# Z05_C8V_02.net
KiCad netlist of a schematic drawn in EAGLE
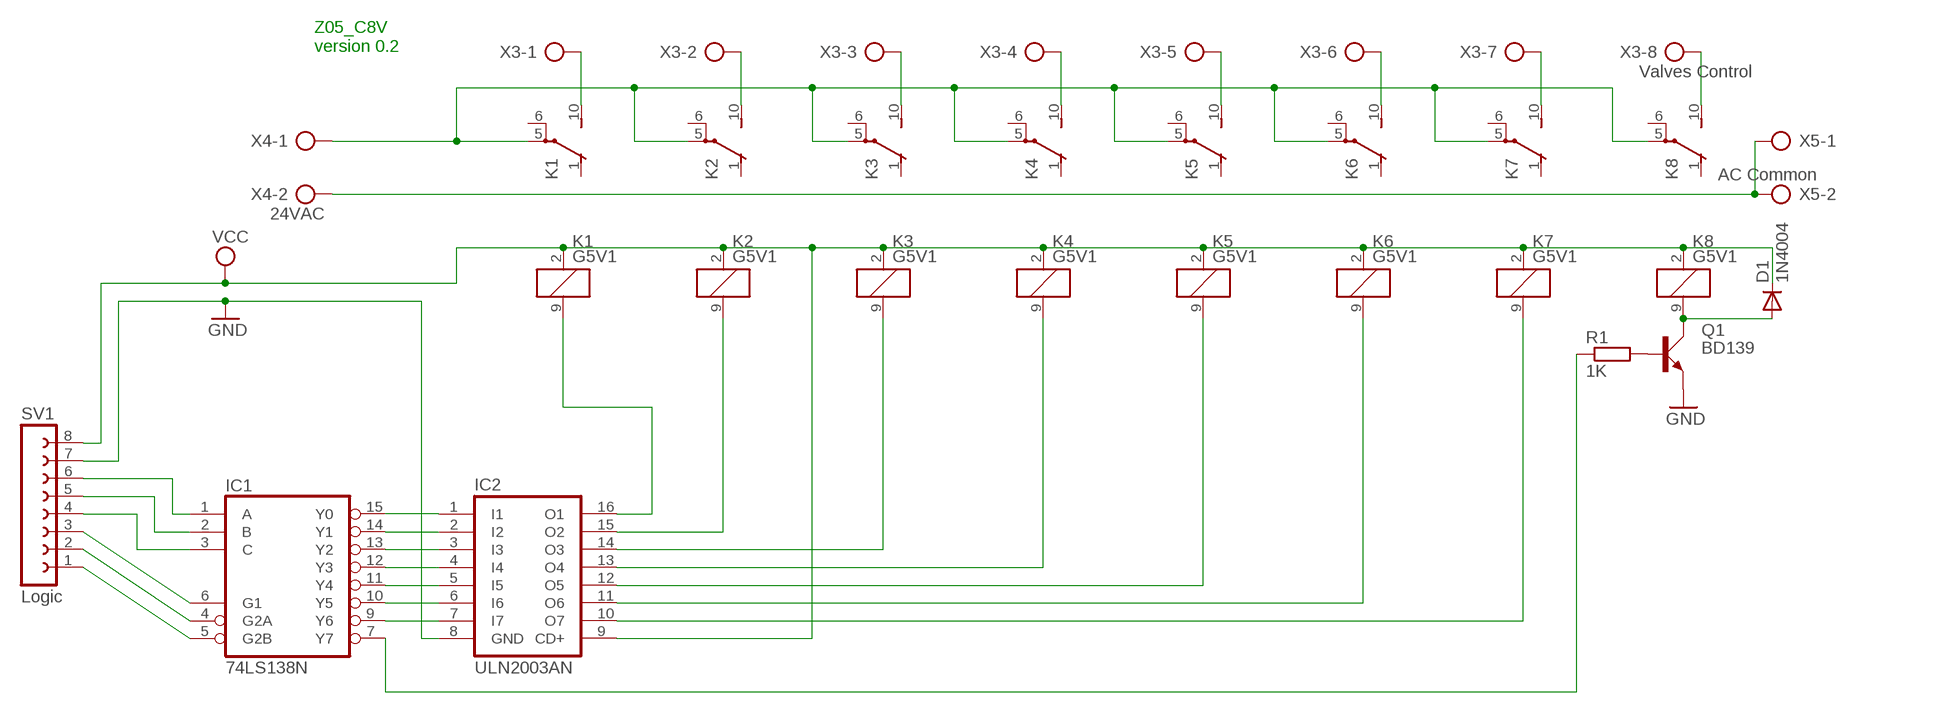
[diagram p0: schematic, sheet 1]

(export (version "E")
  (design (tool "Eeschema 10.0.6"))
  (components
    (comp (ref "D1")
      (value "1N4004")
      (footprint "eagle-import:DO41-10")
      (libsource (lib "eagle-import") (part "1N4004"))
    )
    (comp (ref "IC1")
      (value "74LS138N")
      (footprint "eagle-import:DIL16")
      (libsource (lib "eagle-import") (part "74138NLS"))
    )
    (comp (ref "IC2")
      (value "ULN2003AN")
      (footprint "eagle-import:DIL16")
      (libsource (lib "eagle-import") (part "ULN2003AN"))
    )
    (comp (ref "K1")
      (value "G5V1")
      (footprint "eagle-import:G5V1")
      (fields (field (name "MPN") "G5V-1-DC24"))
      (libsource (lib "eagle-import") (part "G5V1"))
    )
    (comp (ref "K2")
      (value "G5V1")
      (footprint "eagle-import:G5V1")
      (fields (field (name "MPN") "G5V-1-DC24"))
      (libsource (lib "eagle-import") (part "G5V1"))
    )
    (comp (ref "K3")
      (value "G5V1")
      (footprint "eagle-import:G5V1")
      (fields (field (name "MPN") "G5V-1-DC24"))
      (libsource (lib "eagle-import") (part "G5V1"))
    )
    (comp (ref "K4")
      (value "G5V1")
      (footprint "eagle-import:G5V1")
      (fields (field (name "MPN") "G5V-1-DC24"))
      (libsource (lib "eagle-import") (part "G5V1"))
    )
    (comp (ref "K5")
      (value "G5V1")
      (footprint "eagle-import:G5V1")
      (fields (field (name "MPN") "G5V-1-DC24"))
      (libsource (lib "eagle-import") (part "G5V1"))
    )
    (comp (ref "K6")
      (value "G5V1")
      (footprint "eagle-import:G5V1")
      (fields (field (name "MPN") "G5V-1-DC24"))
      (libsource (lib "eagle-import") (part "G5V1"))
    )
    (comp (ref "K7")
      (value "G5V1")
      (footprint "eagle-import:G5V1")
      (fields (field (name "MPN") "G5V-1-DC24"))
      (libsource (lib "eagle-import") (part "G5V1"))
    )
    (comp (ref "K8")
      (value "G5V1")
      (footprint "eagle-import:G5V1")
      (fields (field (name "MPN") "G5V-1-DC24"))
      (libsource (lib "eagle-import") (part "G5V1"))
    )
    (comp (ref "Q1")
      (value "BD139")
      (footprint "eagle-import:TO126AV")
      (libsource (lib "eagle-import") (part "BD139"))
    )
    (comp (ref "R1")
      (value "1K")
      (footprint "eagle-import:0204_7")
      (libsource (lib "eagle-import") (part "R-EU_0204/7"))
    )
    (comp (ref "SV1")
      (value "Logic")
      (footprint "eagle-import:FE08")
      (libsource (lib "eagle-import") (part "FE08-1"))
    )
    (comp (ref "X3")
      (value "Valves Control")
      (footprint "eagle-import:AK500_8")
      (libsource (lib "eagle-import") (part "AK500/8"))
    )
    (comp (ref "X4")
      (value "24VAC")
      (footprint "eagle-import:AK500_2")
      (libsource (lib "eagle-import") (part "AK500/2"))
    )
    (comp (ref "X5")
      (value "AC Common")
      (footprint "eagle-import:AK500_2")
      (libsource (lib "eagle-import") (part "AK500/2"))
    )
  )
  (nets
    (net (code "1") (name "GND") (class "Default")
      (node (ref "IC2") (pin "8") (pinfunction "GND_8") (pintype "power_in"))
      (node (ref "Q1") (pin "E") (pinfunction "E_E") (pintype "passive"))
      (node (ref "SV1") (pin "7") (pinfunction "7_7") (pintype "passive"))
    )
    (net (code "2") (name "Net-(IC1A-A)") (class "Default")
      (node (ref "IC1") (pin "1") (pinfunction "A_1") (pintype "input"))
      (node (ref "SV1") (pin "6") (pinfunction "6_6") (pintype "passive"))
    )
    (net (code "3") (name "Net-(IC1A-B)") (class "Default")
      (node (ref "IC1") (pin "2") (pinfunction "B_2") (pintype "input"))
      (node (ref "SV1") (pin "5") (pinfunction "5_5") (pintype "passive"))
    )
    (net (code "4") (name "Net-(IC1A-C)") (class "Default")
      (node (ref "IC1") (pin "3") (pinfunction "C_3") (pintype "input"))
      (node (ref "SV1") (pin "4") (pinfunction "4_4") (pintype "passive"))
    )
    (net (code "5") (name "Net-(IC1A-G1)") (class "Default")
      (node (ref "IC1") (pin "6") (pinfunction "G1_6") (pintype "input"))
      (node (ref "SV1") (pin "3") (pinfunction "3_3") (pintype "passive"))
    )
    (net (code "6") (name "Net-(IC1A-G2A)") (class "Default")
      (node (ref "IC1") (pin "4") (pinfunction "G2A_4") (pintype "input"))
      (node (ref "SV1") (pin "2") (pinfunction "2_2") (pintype "passive"))
    )
    (net (code "7") (name "Net-(IC1A-G2B)") (class "Default")
      (node (ref "IC1") (pin "5") (pinfunction "G2B_5") (pintype "input"))
      (node (ref "SV1") (pin "1") (pinfunction "1_1") (pintype "passive"))
    )
    (net (code "8") (name "Net-(IC1A-Y0)") (class "Default")
      (node (ref "IC1") (pin "15") (pinfunction "Y0_15") (pintype "output"))
      (node (ref "IC2") (pin "1") (pinfunction "I1_1") (pintype "input"))
    )
    (net (code "9") (name "Net-(IC1A-Y1)") (class "Default")
      (node (ref "IC1") (pin "14") (pinfunction "Y1_14") (pintype "output"))
      (node (ref "IC2") (pin "2") (pinfunction "I2_2") (pintype "input"))
    )
    (net (code "10") (name "Net-(IC1A-Y2)") (class "Default")
      (node (ref "IC1") (pin "13") (pinfunction "Y2_13") (pintype "output"))
      (node (ref "IC2") (pin "3") (pinfunction "I3_3") (pintype "input"))
    )
    (net (code "11") (name "Net-(IC1A-Y3)") (class "Default")
      (node (ref "IC1") (pin "12") (pinfunction "Y3_12") (pintype "output"))
      (node (ref "IC2") (pin "4") (pinfunction "I4_4") (pintype "input"))
    )
    (net (code "12") (name "Net-(IC1A-Y4)") (class "Default")
      (node (ref "IC1") (pin "11") (pinfunction "Y4_11") (pintype "output"))
      (node (ref "IC2") (pin "5") (pinfunction "I5_5") (pintype "input"))
    )
    (net (code "13") (name "Net-(IC1A-Y5)") (class "Default")
      (node (ref "IC1") (pin "10") (pinfunction "Y5_10") (pintype "output"))
      (node (ref "IC2") (pin "6") (pinfunction "I6_6") (pintype "input"))
    )
    (net (code "14") (name "Net-(IC1A-Y6)") (class "Default")
      (node (ref "IC1") (pin "9") (pinfunction "Y6_9") (pintype "output"))
      (node (ref "IC2") (pin "7") (pinfunction "I7_7") (pintype "input"))
    )
    (net (code "15") (name "Net-(IC1A-Y7)") (class "Default")
      (node (ref "IC1") (pin "7") (pinfunction "Y7_7") (pintype "output"))
      (node (ref "R1") (pin "1") (pinfunction "1_1") (pintype "passive"))
    )
    (net (code "16") (name "Net-(IC2-O1)") (class "Default")
      (node (ref "IC2") (pin "16") (pinfunction "O1_16") (pintype "open_collector"))
      (node (ref "K1") (pin "9") (pinfunction "2_9") (pintype "passive"))
    )
    (net (code "17") (name "Net-(IC2-O2)") (class "Default")
      (node (ref "IC2") (pin "15") (pinfunction "O2_15") (pintype "open_collector"))
      (node (ref "K2") (pin "9") (pinfunction "2_9") (pintype "passive"))
    )
    (net (code "18") (name "Net-(IC2-O3)") (class "Default")
      (node (ref "IC2") (pin "14") (pinfunction "O3_14") (pintype "open_collector"))
      (node (ref "K3") (pin "9") (pinfunction "2_9") (pintype "passive"))
    )
    (net (code "19") (name "Net-(IC2-O4)") (class "Default")
      (node (ref "IC2") (pin "13") (pinfunction "O4_13") (pintype "open_collector"))
      (node (ref "K4") (pin "9") (pinfunction "2_9") (pintype "passive"))
    )
    (net (code "20") (name "Net-(IC2-O5)") (class "Default")
      (node (ref "IC2") (pin "12") (pinfunction "O5_12") (pintype "open_collector"))
      (node (ref "K5") (pin "9") (pinfunction "2_9") (pintype "passive"))
    )
    (net (code "21") (name "Net-(IC2-O6)") (class "Default")
      (node (ref "IC2") (pin "11") (pinfunction "O6_11") (pintype "open_collector"))
      (node (ref "K6") (pin "9") (pinfunction "2_9") (pintype "passive"))
    )
    (net (code "22") (name "Net-(IC2-O7)") (class "Default")
      (node (ref "IC2") (pin "10") (pinfunction "O7_10") (pintype "open_collector"))
      (node (ref "K7") (pin "9") (pinfunction "2_9") (pintype "passive"))
    )
    (net (code "23") (name "Net-(K1B-S)") (class "Default")
      (node (ref "K1") (pin "10") (pinfunction "S_10") (pintype "passive"))
      (node (ref "X3") (pin "1") (pinfunction "KL_1") (pintype "passive"))
    )
    (net (code "24") (name "Net-(K2B-S)") (class "Default")
      (node (ref "K2") (pin "10") (pinfunction "S_10") (pintype "passive"))
      (node (ref "X3") (pin "2") (pinfunction "KL_2") (pintype "passive"))
    )
    (net (code "25") (name "Net-(K3B-S)") (class "Default")
      (node (ref "K3") (pin "10") (pinfunction "S_10") (pintype "passive"))
      (node (ref "X3") (pin "3") (pinfunction "KL_3") (pintype "passive"))
    )
    (net (code "26") (name "Net-(K4B-S)") (class "Default")
      (node (ref "K4") (pin "10") (pinfunction "S_10") (pintype "passive"))
      (node (ref "X3") (pin "4") (pinfunction "KL_4") (pintype "passive"))
    )
    (net (code "27") (name "Net-(K5B-S)") (class "Default")
      (node (ref "K5") (pin "10") (pinfunction "S_10") (pintype "passive"))
      (node (ref "X3") (pin "5") (pinfunction "KL_5") (pintype "passive"))
    )
    (net (code "28") (name "Net-(K6B-S)") (class "Default")
      (node (ref "K6") (pin "10") (pinfunction "S_10") (pintype "passive"))
      (node (ref "X3") (pin "6") (pinfunction "KL_6") (pintype "passive"))
    )
    (net (code "29") (name "Net-(K7B-S)") (class "Default")
      (node (ref "K7") (pin "10") (pinfunction "S_10") (pintype "passive"))
      (node (ref "X3") (pin "7") (pinfunction "KL_7") (pintype "passive"))
    )
    (net (code "30") (name "Net-(K8A-2)") (class "Default")
      (node (ref "D1") (pin "A") (pinfunction "A_A") (pintype "passive"))
      (node (ref "K8") (pin "9") (pinfunction "2_9") (pintype "passive"))
      (node (ref "Q1") (pin "C") (pinfunction "C_C") (pintype "passive"))
    )
    (net (code "31") (name "Net-(K8B-S)") (class "Default")
      (node (ref "K8") (pin "10") (pinfunction "S_10") (pintype "passive"))
      (node (ref "X3") (pin "8") (pinfunction "KL_8") (pintype "passive"))
    )
    (net (code "32") (name "Net-(Q1-PadB)") (class "Default")
      (node (ref "Q1") (pin "B") (pinfunction "B_B") (pintype "passive"))
      (node (ref "R1") (pin "2") (pinfunction "2_2") (pintype "passive"))
    )
    (net (code "33") (name "Net-(X4A-KL)") (class "Default")
      (node (ref "K1") (pin "5") (pinfunction "P_5") (pintype "passive"))
      (node (ref "K2") (pin "5") (pinfunction "P_5") (pintype "passive"))
      (node (ref "K3") (pin "5") (pinfunction "P_5") (pintype "passive"))
      (node (ref "K4") (pin "5") (pinfunction "P_5") (pintype "passive"))
      (node (ref "K5") (pin "5") (pinfunction "P_5") (pintype "passive"))
      (node (ref "K6") (pin "5") (pinfunction "P_5") (pintype "passive"))
      (node (ref "K7") (pin "5") (pinfunction "P_5") (pintype "passive"))
      (node (ref "K8") (pin "5") (pinfunction "P_5") (pintype "passive"))
      (node (ref "X4") (pin "1") (pinfunction "KL_1") (pintype "passive"))
    )
    (net (code "34") (name "Net-(X4B-KL)") (class "Default")
      (node (ref "X4") (pin "2") (pinfunction "KL_2") (pintype "passive"))
      (node (ref "X5") (pin "1") (pinfunction "KL_1") (pintype "passive"))
      (node (ref "X5") (pin "2") (pinfunction "KL_2") (pintype "passive"))
    )
    (net (code "35") (name "VCC") (class "Default")
      (node (ref "D1") (pin "C") (pinfunction "C_C") (pintype "passive"))
      (node (ref "IC2") (pin "9") (pinfunction "CD+_9") (pintype "passive"))
      (node (ref "K1") (pin "2") (pinfunction "1_2") (pintype "passive"))
      (node (ref "K2") (pin "2") (pinfunction "1_2") (pintype "passive"))
      (node (ref "K3") (pin "2") (pinfunction "1_2") (pintype "passive"))
      (node (ref "K4") (pin "2") (pinfunction "1_2") (pintype "passive"))
      (node (ref "K5") (pin "2") (pinfunction "1_2") (pintype "passive"))
      (node (ref "K6") (pin "2") (pinfunction "1_2") (pintype "passive"))
      (node (ref "K7") (pin "2") (pinfunction "1_2") (pintype "passive"))
      (node (ref "K8") (pin "2") (pinfunction "1_2") (pintype "passive"))
      (node (ref "SV1") (pin "8") (pinfunction "8_8") (pintype "passive"))
    )
    (net (code "36") (name "unconnected-(K1B-O-Pad1)") (class "Default")
      (node (ref "K1") (pin "1") (pinfunction "O_1") (pintype "passive"))
    )
    (net (code "37") (name "unconnected-(K1B-P-Pad6)") (class "Default")
      (node (ref "K1") (pin "6") (pinfunction "P_6") (pintype "passive"))
    )
    (net (code "38") (name "unconnected-(K2B-O-Pad1)") (class "Default")
      (node (ref "K2") (pin "1") (pinfunction "O_1") (pintype "passive"))
    )
    (net (code "39") (name "unconnected-(K2B-P-Pad6)") (class "Default")
      (node (ref "K2") (pin "6") (pinfunction "P_6") (pintype "passive"))
    )
    (net (code "40") (name "unconnected-(K3B-O-Pad1)") (class "Default")
      (node (ref "K3") (pin "1") (pinfunction "O_1") (pintype "passive"))
    )
    (net (code "41") (name "unconnected-(K3B-P-Pad6)") (class "Default")
      (node (ref "K3") (pin "6") (pinfunction "P_6") (pintype "passive"))
    )
    (net (code "42") (name "unconnected-(K4B-O-Pad1)") (class "Default")
      (node (ref "K4") (pin "1") (pinfunction "O_1") (pintype "passive"))
    )
    (net (code "43") (name "unconnected-(K4B-P-Pad6)") (class "Default")
      (node (ref "K4") (pin "6") (pinfunction "P_6") (pintype "passive"))
    )
    (net (code "44") (name "unconnected-(K5B-O-Pad1)") (class "Default")
      (node (ref "K5") (pin "1") (pinfunction "O_1") (pintype "passive"))
    )
    (net (code "45") (name "unconnected-(K5B-P-Pad6)") (class "Default")
      (node (ref "K5") (pin "6") (pinfunction "P_6") (pintype "passive"))
    )
    (net (code "46") (name "unconnected-(K6B-O-Pad1)") (class "Default")
      (node (ref "K6") (pin "1") (pinfunction "O_1") (pintype "passive"))
    )
    (net (code "47") (name "unconnected-(K6B-P-Pad6)") (class "Default")
      (node (ref "K6") (pin "6") (pinfunction "P_6") (pintype "passive"))
    )
    (net (code "48") (name "unconnected-(K7B-O-Pad1)") (class "Default")
      (node (ref "K7") (pin "1") (pinfunction "O_1") (pintype "passive"))
    )
    (net (code "49") (name "unconnected-(K7B-P-Pad6)") (class "Default")
      (node (ref "K7") (pin "6") (pinfunction "P_6") (pintype "passive"))
    )
    (net (code "50") (name "unconnected-(K8B-O-Pad1)") (class "Default")
      (node (ref "K8") (pin "1") (pinfunction "O_1") (pintype "passive"))
    )
    (net (code "51") (name "unconnected-(K8B-P-Pad6)") (class "Default")
      (node (ref "K8") (pin "6") (pinfunction "P_6") (pintype "passive"))
    )
  )
)
